# Deathsound_power_amp_channel.net
KiCad netlist of a schematic drawn in Altium Designer
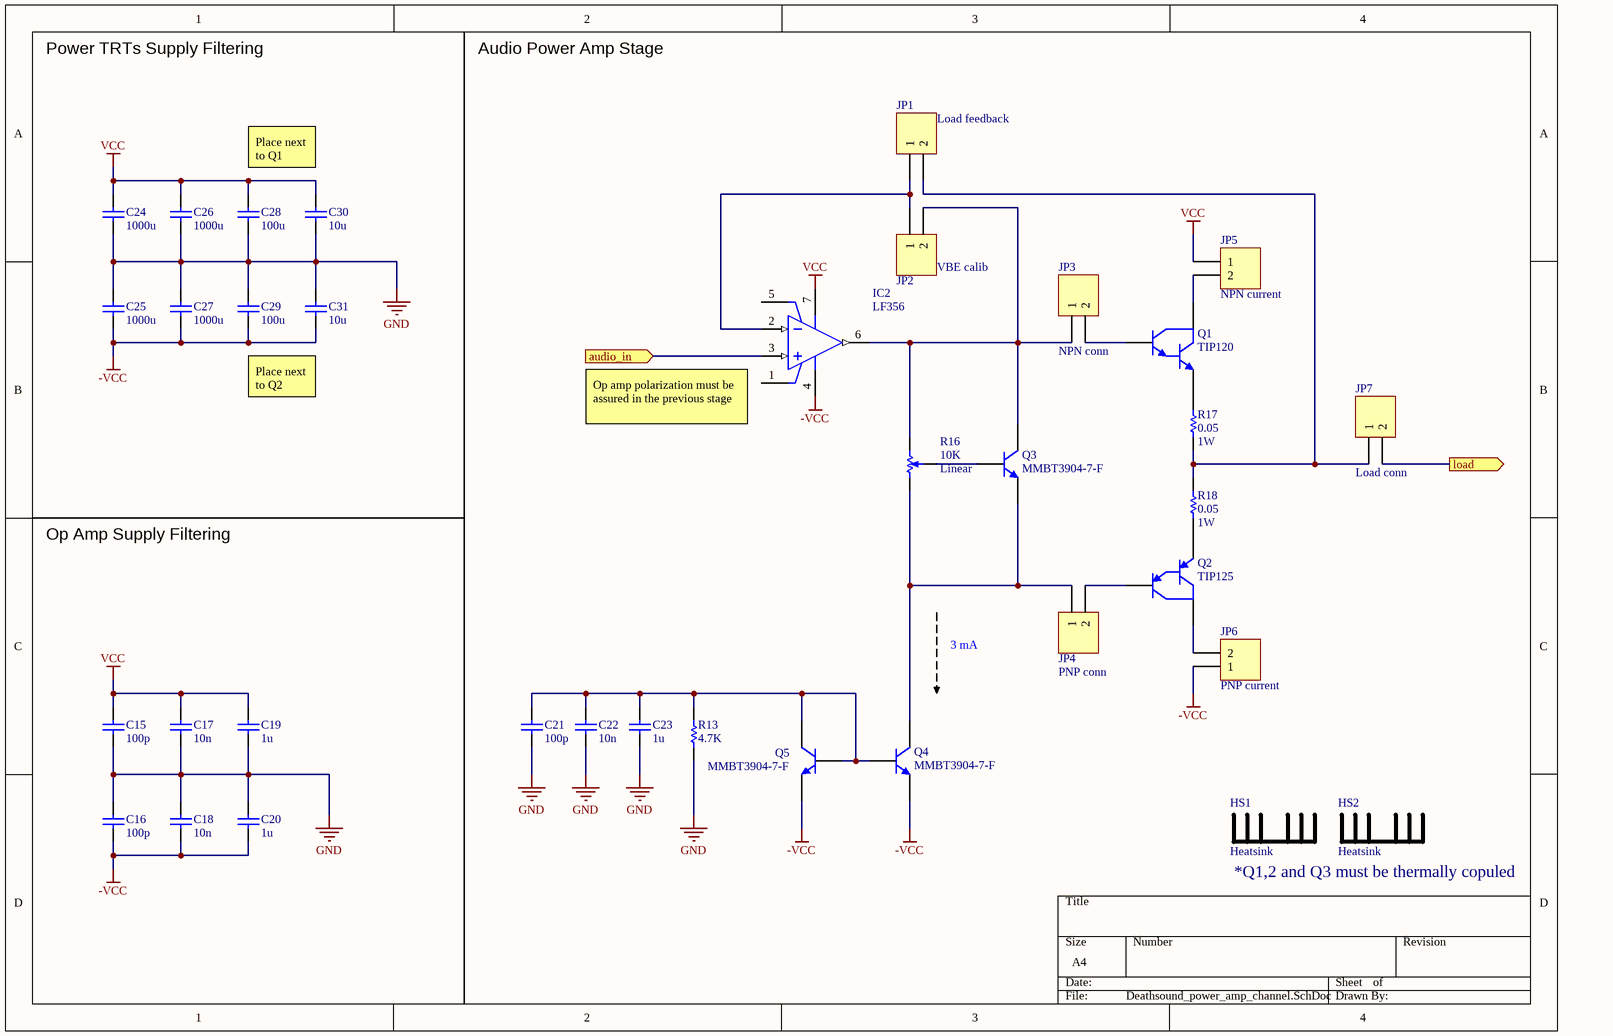
[diagram p0: Deathsound_power_amp_channel.SchDoc]

(export (version "E")
  (design (tool "Eeschema 10.0.6"))
  (components
    (comp (ref "C15")
      (value "100p")
      (footprint "C0805")
      (description "Capacitor")
      (libsource (lib "nucleoduro_lib_audio") (part "Capacitor"))
    )
    (comp (ref "C16")
      (value "100p")
      (footprint "C0805")
      (description "Capacitor")
      (libsource (lib "nucleoduro_lib_audio") (part "Capacitor"))
    )
    (comp (ref "C17")
      (value "10n")
      (footprint "C0805")
      (description "Capacitor")
      (libsource (lib "nucleoduro_lib_audio") (part "Capacitor"))
    )
    (comp (ref "C18")
      (value "10n")
      (footprint "C0805")
      (description "Capacitor")
      (libsource (lib "nucleoduro_lib_audio") (part "Capacitor"))
    )
    (comp (ref "C19")
      (value "1u")
      (footprint "C0805")
      (description "Capacitor")
      (libsource (lib "nucleoduro_lib_audio") (part "Capacitor"))
    )
    (comp (ref "C20")
      (value "1u")
      (footprint "C0805")
      (description "Capacitor")
      (libsource (lib "nucleoduro_lib_audio") (part "Capacitor"))
    )
    (comp (ref "C21")
      (value "100p")
      (footprint "C0805")
      (description "Capacitor")
      (libsource (lib "nucleoduro_lib_audio") (part "Capacitor"))
    )
    (comp (ref "C22")
      (value "10n")
      (footprint "C0805")
      (description "Capacitor")
      (libsource (lib "nucleoduro_lib_audio") (part "Capacitor"))
    )
    (comp (ref "C23")
      (value "1u")
      (footprint "C0805")
      (description "Capacitor")
      (libsource (lib "nucleoduro_lib_audio") (part "Capacitor"))
    )
    (comp (ref "C24")
      (value "1000u")
      (footprint "C0805")
      (description "Capacitor")
      (libsource (lib "nucleoduro_lib_audio") (part "Capacitor"))
    )
    (comp (ref "C25")
      (value "1000u")
      (footprint "C0805")
      (description "Capacitor")
      (libsource (lib "nucleoduro_lib_audio") (part "Capacitor"))
    )
    (comp (ref "C26")
      (value "1000u")
      (footprint "C0805")
      (description "Capacitor")
      (libsource (lib "nucleoduro_lib_audio") (part "Capacitor"))
    )
    (comp (ref "C27")
      (value "1000u")
      (footprint "C0805")
      (description "Capacitor")
      (libsource (lib "nucleoduro_lib_audio") (part "Capacitor"))
    )
    (comp (ref "C28")
      (value "100u")
      (footprint "C0805")
      (description "Capacitor")
      (libsource (lib "nucleoduro_lib_audio") (part "Capacitor"))
    )
    (comp (ref "C29")
      (value "100u")
      (footprint "C0805")
      (description "Capacitor")
      (libsource (lib "nucleoduro_lib_audio") (part "Capacitor"))
    )
    (comp (ref "C30")
      (value "10u")
      (footprint "C0805")
      (description "Capacitor")
      (libsource (lib "nucleoduro_lib_audio") (part "Capacitor"))
    )
    (comp (ref "C31")
      (value "10u")
      (footprint "C0805")
      (description "Capacitor")
      (libsource (lib "nucleoduro_lib_audio") (part "Capacitor"))
    )
    (comp (ref "HS1")
      (value "Heatsink")
      (footprint "MC33289")
      (description "Q1 Heatsink")
      (libsource (lib "nucleoduro_lib_audio") (part "Heatsink (MC33289)"))
    )
    (comp (ref "HS2")
      (value "Heatsink")
      (footprint "MC33289")
      (description "Q2 Heatsink")
      (libsource (lib "nucleoduro_lib_audio") (part "Heatsink (MC33289)"))
    )
    (comp (ref "IC2")
      (value "LF356")
      (footprint "SOIC127P600X175-8N")
      (libsource (lib "nucleoduro_lib_audio") (part "LF356"))
    )
    (comp (ref "JP1")
      (value "Load feedback")
      (footprint "HDR1X2")
      (description "Header, 2-Pin")
      (libsource (lib "") (part "Header 2_1"))
    )
    (comp (ref "JP2")
      (value "VBE calib")
      (footprint "HDR1X2")
      (description "Header, 2-Pin")
      (libsource (lib "nucleoduro_lib_audio") (part "Header 2"))
    )
    (comp (ref "JP3")
      (value "NPN conn")
      (footprint "HDR1X2")
      (description "Header, 2-Pin")
      (libsource (lib "") (part "Header 2_1"))
    )
    (comp (ref "JP4")
      (value "PNP conn")
      (footprint "HDR1X2")
      (description "Header, 2-Pin")
      (libsource (lib "nucleoduro_lib_audio") (part "Header 2"))
    )
    (comp (ref "JP5")
      (value "NPN current")
      (footprint "HDR1X2")
      (description "Header, 2-Pin")
      (libsource (lib "") (part "Header 2_2"))
    )
    (comp (ref "JP6")
      (value "PNP current")
      (footprint "HDR1X2")
      (description "Header, 2-Pin")
      (libsource (lib "") (part "Header 2_1"))
    )
    (comp (ref "JP7")
      (value "Load conn")
      (footprint "HDR1X2")
      (description "Header, 2-Pin")
      (libsource (lib "") (part "Header 2_1"))
    )
    (comp (ref "Q1")
      (value "TIP120")
      (footprint "TO-220")
      (description "NPN Darlington Bipolar Transistor")
      (libsource (lib "nucleoduro_lib_audio") (part "TIP120/121/122"))
    )
    (comp (ref "Q2")
      (value "TIP125")
      (footprint "TO-220")
      (description "PNP Darlington Bipolar Transistor")
      (libsource (lib "nucleoduro_lib_audio") (part "TIP125/126/127"))
    )
    (comp (ref "Q3")
      (value "MMBT3904-7-F")
      (footprint "SOT95P240X110-3N")
      (description "NPN General Purpose Amplifier SMD")
      (libsource (lib "nucleoduro_lib_audio") (part "MMBT3904-7-F"))
    )
    (comp (ref "Q4")
      (value "MMBT3904-7-F")
      (footprint "SOT95P240X110-3N")
      (description "NPN General Purpose Amplifier SMD")
      (libsource (lib "nucleoduro_lib_audio") (part "MMBT3904-7-F"))
    )
    (comp (ref "Q5")
      (value "MMBT3904-7-F")
      (footprint "SOT95P240X110-3N")
      (description "NPN General Purpose Amplifier SMD")
      (libsource (lib "nucleoduro_lib_audio") (part "MMBT3904-7-F"))
    )
    (comp (ref "R13")
      (value "4.7K")
      (footprint "R0805")
      (description "Resistor")
      (libsource (lib "nucleoduro_lib_audio") (part "Resistor"))
    )
    (comp (ref "R16")
      (value "10K")
      (footprint "Res Pot Square Trimm")
      (description "Square Trimming Potentiometer")
      (fields (field (name "TYPE") "Linear"))
      (libsource (lib "nucleoduro_lib_audio") (part "Res Pot"))
    )
    (comp (ref "R17")
      (value "0.05")
      (footprint "R2512")
      (description "Resistor")
      (fields (field (name "POWER") "1W"))
      (libsource (lib "nucleoduro_lib_audio") (part "Resistor"))
    )
    (comp (ref "R18")
      (value "0.05")
      (footprint "R2512")
      (description "Resistor")
      (fields (field (name "POWER") "1W"))
      (libsource (lib "nucleoduro_lib_audio") (part "Resistor"))
    )
  )
  (nets
    (net (code "1") (name "-VCC") (class "Default")
      (node (ref "C16") (pin "1") (pinfunction "1_1") (pintype "passive"))
      (node (ref "C18") (pin "1") (pinfunction "1_1") (pintype "passive"))
      (node (ref "C20") (pin "1") (pinfunction "1_1") (pintype "passive"))
      (node (ref "C25") (pin "1") (pinfunction "1_1") (pintype "passive"))
      (node (ref "C27") (pin "1") (pinfunction "1_1") (pintype "passive"))
      (node (ref "C29") (pin "1") (pinfunction "1_1") (pintype "passive"))
      (node (ref "C31") (pin "1") (pinfunction "1_1") (pintype "passive"))
      (node (ref "IC2") (pin "4") (pinfunction "V-_4") (pintype "power_in"))
      (node (ref "JP6") (pin "1") (pinfunction "1_1") (pintype "passive"))
      (node (ref "Q4") (pin "2") (pinfunction "E_2") (pintype "passive"))
      (node (ref "Q5") (pin "2") (pinfunction "E_2") (pintype "passive"))
    )
    (net (code "2") (name "/audio_in") (class "Default")
      (node (ref "IC2") (pin "3") (pinfunction "IN+_3") (pintype "input"))
    )
    (net (code "3") (name "/load") (class "Default")
      (node (ref "JP7") (pin "2") (pinfunction "2_2") (pintype "passive"))
    )
    (net (code "4") (name "GND") (class "Default")
      (node (ref "C15") (pin "1") (pinfunction "1_1") (pintype "passive"))
      (node (ref "C16") (pin "2") (pinfunction "2_2") (pintype "passive"))
      (node (ref "C17") (pin "1") (pinfunction "1_1") (pintype "passive"))
      (node (ref "C18") (pin "2") (pinfunction "2_2") (pintype "passive"))
      (node (ref "C19") (pin "1") (pinfunction "1_1") (pintype "passive"))
      (node (ref "C20") (pin "2") (pinfunction "2_2") (pintype "passive"))
      (node (ref "C21") (pin "1") (pinfunction "1_1") (pintype "passive"))
      (node (ref "C22") (pin "1") (pinfunction "1_1") (pintype "passive"))
      (node (ref "C23") (pin "1") (pinfunction "1_1") (pintype "passive"))
      (node (ref "C24") (pin "1") (pinfunction "1_1") (pintype "passive"))
      (node (ref "C25") (pin "2") (pinfunction "2_2") (pintype "passive"))
      (node (ref "C26") (pin "1") (pinfunction "1_1") (pintype "passive"))
      (node (ref "C27") (pin "2") (pinfunction "2_2") (pintype "passive"))
      (node (ref "C28") (pin "1") (pinfunction "1_1") (pintype "passive"))
      (node (ref "C29") (pin "2") (pinfunction "2_2") (pintype "passive"))
      (node (ref "C30") (pin "1") (pinfunction "1_1") (pintype "passive"))
      (node (ref "C31") (pin "2") (pinfunction "2_2") (pintype "passive"))
      (node (ref "R13") (pin "2") (pinfunction "2_2") (pintype "passive"))
    )
    (net (code "5") (name "Net-(IC2-IN-)") (class "Default")
      (node (ref "IC2") (pin "2") (pinfunction "IN-_2") (pintype "input"))
      (node (ref "JP1") (pin "1") (pinfunction "1_1") (pintype "passive"))
      (node (ref "JP2") (pin "1") (pinfunction "1_1") (pintype "passive"))
    )
    (net (code "6") (name "Net-(IC2-OUT)") (class "Default")
      (node (ref "IC2") (pin "6") (pinfunction "OUT_6") (pintype "output"))
      (node (ref "JP2") (pin "2") (pinfunction "2_2") (pintype "passive"))
      (node (ref "JP3") (pin "1") (pinfunction "1_1") (pintype "passive"))
      (node (ref "Q3") (pin "3") (pinfunction "C_3") (pintype "passive"))
      (node (ref "R16") (pin "1") (pinfunction "1_1") (pintype "passive"))
    )
    (net (code "7") (name "Net-(JP1-Pad2)") (class "Default")
      (node (ref "JP1") (pin "2") (pinfunction "2_2") (pintype "passive"))
      (node (ref "JP7") (pin "1") (pinfunction "1_1") (pintype "passive"))
      (node (ref "R17") (pin "1") (pinfunction "1_1") (pintype "passive"))
      (node (ref "R18") (pin "2") (pinfunction "2_2") (pintype "passive"))
    )
    (net (code "8") (name "Net-(Q1-B)") (class "Default")
      (node (ref "JP3") (pin "2") (pinfunction "2_2") (pintype "passive"))
      (node (ref "Q1") (pin "1") (pinfunction "B_1") (pintype "passive"))
    )
    (net (code "9") (name "Net-(Q1-C)") (class "Default")
      (node (ref "JP5") (pin "2") (pinfunction "2_2") (pintype "passive"))
      (node (ref "Q1") (pin "2") (pinfunction "C_2") (pintype "passive"))
    )
    (net (code "10") (name "Net-(Q1-E)") (class "Default")
      (node (ref "Q1") (pin "3") (pinfunction "E_3") (pintype "passive"))
      (node (ref "R17") (pin "2") (pinfunction "2_2") (pintype "passive"))
    )
    (net (code "11") (name "Net-(Q2-B)") (class "Default")
      (node (ref "JP4") (pin "2") (pinfunction "2_2") (pintype "passive"))
      (node (ref "Q2") (pin "1") (pinfunction "B_1") (pintype "passive"))
    )
    (net (code "12") (name "Net-(Q2-C)") (class "Default")
      (node (ref "JP6") (pin "2") (pinfunction "2_2") (pintype "passive"))
      (node (ref "Q2") (pin "2") (pinfunction "C_2") (pintype "passive"))
    )
    (net (code "13") (name "Net-(Q2-E)") (class "Default")
      (node (ref "Q2") (pin "3") (pinfunction "E_3") (pintype "passive"))
      (node (ref "R18") (pin "1") (pinfunction "1_1") (pintype "passive"))
    )
    (net (code "14") (name "Net-(Q3-B)") (class "Default")
      (node (ref "Q3") (pin "1") (pinfunction "B_1") (pintype "passive"))
      (node (ref "R16") (pin "2") (pinfunction "2_2") (pintype "passive"))
    )
    (net (code "15") (name "Net-(Q3-E)") (class "Default")
      (node (ref "JP4") (pin "1") (pinfunction "1_1") (pintype "passive"))
      (node (ref "Q3") (pin "2") (pinfunction "E_2") (pintype "passive"))
      (node (ref "Q4") (pin "3") (pinfunction "C_3") (pintype "passive"))
      (node (ref "R16") (pin "3") (pinfunction "3_3") (pintype "passive"))
    )
    (net (code "16") (name "Net-(Q4-B)") (class "Default")
      (node (ref "C21") (pin "2") (pinfunction "2_2") (pintype "passive"))
      (node (ref "C22") (pin "2") (pinfunction "2_2") (pintype "passive"))
      (node (ref "C23") (pin "2") (pinfunction "2_2") (pintype "passive"))
      (node (ref "Q4") (pin "1") (pinfunction "B_1") (pintype "passive"))
      (node (ref "Q5") (pin "1") (pinfunction "B_1") (pintype "passive"))
      (node (ref "Q5") (pin "3") (pinfunction "C_3") (pintype "passive"))
      (node (ref "R13") (pin "1") (pinfunction "1_1") (pintype "passive"))
    )
    (net (code "17") (name "VCC") (class "Default")
      (node (ref "C15") (pin "2") (pinfunction "2_2") (pintype "passive"))
      (node (ref "C17") (pin "2") (pinfunction "2_2") (pintype "passive"))
      (node (ref "C19") (pin "2") (pinfunction "2_2") (pintype "passive"))
      (node (ref "C24") (pin "2") (pinfunction "2_2") (pintype "passive"))
      (node (ref "C26") (pin "2") (pinfunction "2_2") (pintype "passive"))
      (node (ref "C28") (pin "2") (pinfunction "2_2") (pintype "passive"))
      (node (ref "C30") (pin "2") (pinfunction "2_2") (pintype "passive"))
      (node (ref "IC2") (pin "7") (pinfunction "V+_7") (pintype "power_in"))
      (node (ref "JP5") (pin "1") (pinfunction "1_1") (pintype "passive"))
    )
    (net (code "18") (name "unconnected-(IC2-BALANCE1-Pad1)") (class "Default")
      (node (ref "IC2") (pin "1") (pinfunction "BALANCE1_1") (pintype "passive"))
    )
    (net (code "19") (name "unconnected-(IC2-BALANCE2-Pad5)") (class "Default")
      (node (ref "IC2") (pin "5") (pinfunction "BALANCE2_5") (pintype "passive"))
    )
  )
)
